# SD_Card.net
KiCad netlist of a schematic drawn in Altium Designer
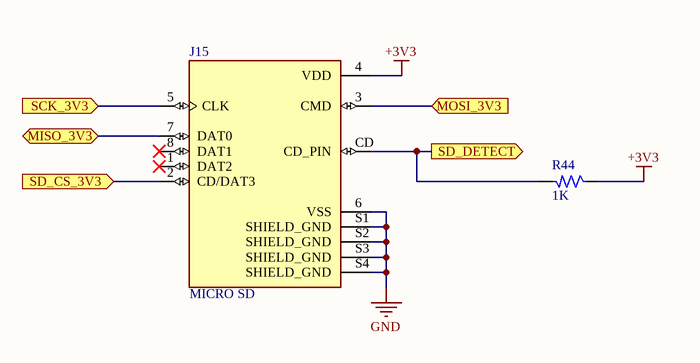
[diagram p0: SD Card.SchDoc]

(export (version "E")
  (design (tool "Eeschema 10.0.6"))
  (components
    (comp (ref "J15")
      (value "MICRO SD")
      (footprint "AMPHENOL_GTFP08131Y2HR")
      (description "GTFP08131Y2HR")
      (libsource (lib "TAREKPCBLIB") (part "MICRO SD"))
    )
    (comp (ref "R44")
      (value "1K")
      (footprint "RES_0805")
      (description "1 kOhms ±1% 0.125W, 1/8W Chip Resistor 0805 (2012 Metric) Moisture Resistant Thick Film")
      (fields (field (name "MANUFACTURER") "Walsin") (field (name "MANUFACTURER PART NUMBER") "WR08X1001FTL"))
      (libsource (lib "ESTEEMPCBLIB") (part "RES_1K-0.125W-1%-0805"))
    )
  )
  (nets
    (net (code "1") (name "+3V3") (class "Default")
      (node (ref "J15") (pin "4") (pinfunction "VDD_4") (pintype "power_in"))
      (node (ref "R44") (pin "1") (pinfunction "1_1") (pintype "passive"))
    )
    (net (code "2") (name "/MISO_3V3") (class "Default")
      (node (ref "J15") (pin "7") (pinfunction "DAT0_7") (pintype "bidirectional"))
    )
    (net (code "3") (name "/MOSI_3V3") (class "Default")
      (node (ref "J15") (pin "3") (pinfunction "CMD_3") (pintype "bidirectional"))
    )
    (net (code "4") (name "/SCK_3V3") (class "Default")
      (node (ref "J15") (pin "5") (pinfunction "CLK_5") (pintype "bidirectional"))
    )
    (net (code "5") (name "/SD_CS_3V3") (class "Default")
      (node (ref "J15") (pin "2") (pinfunction "CD/DAT3_2") (pintype "bidirectional"))
    )
    (net (code "6") (name "/SD_DETECT") (class "Default")
      (node (ref "J15") (pin "CD") (pinfunction "CD_PIN_CD") (pintype "bidirectional"))
      (node (ref "R44") (pin "2") (pinfunction "2_2") (pintype "passive"))
    )
    (net (code "7") (name "GND") (class "Default")
      (node (ref "J15") (pin "6") (pinfunction "VSS_6") (pintype "power_in"))
      (node (ref "J15") (pin "S1") (pinfunction "SHIELD_GND_S1") (pintype "power_in"))
      (node (ref "J15") (pin "S2") (pinfunction "SHIELD_GND_S2") (pintype "power_in"))
      (node (ref "J15") (pin "S3") (pinfunction "SHIELD_GND_S3") (pintype "power_in"))
      (node (ref "J15") (pin "S4") (pinfunction "SHIELD_GND_S4") (pintype "power_in"))
    )
    (net (code "8") (name "unconnected-(J15-DAT1-Pad8)") (class "Default")
      (node (ref "J15") (pin "8") (pinfunction "DAT1_8") (pintype "bidirectional+no_connect"))
    )
    (net (code "9") (name "unconnected-(J15-DAT2-Pad1)") (class "Default")
      (node (ref "J15") (pin "1") (pinfunction "DAT2_1") (pintype "bidirectional+no_connect"))
    )
  )
)
